# esquematico.net
KiCad netlist of a schematic drawn in Altium Designer
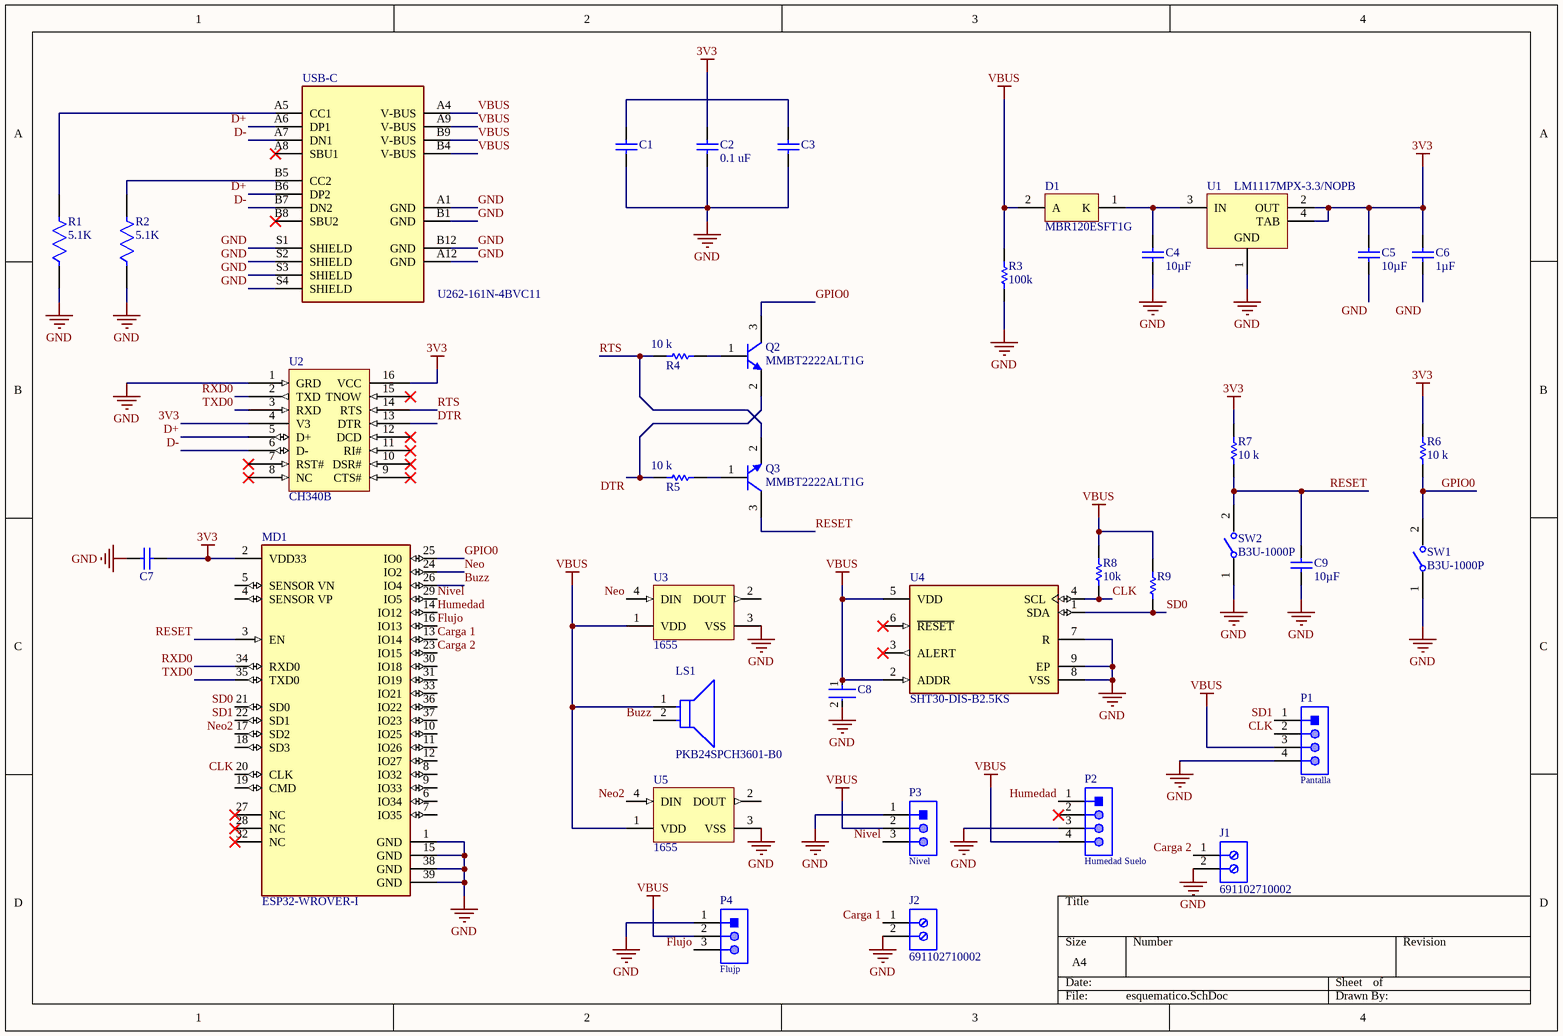
[diagram p0: esquematico.SchDoc]

(export (version "E")
  (design (tool "Eeschema 10.0.6"))
  (components
    (comp (ref "C1")
      (value "C0805C106K4PACTU")
      (footprint "CAPC2013X140X50ML20T25")
      (description "10µF ±10% 16V Ceramic Capacitor X5R 0805 (2012 Metric)")
      (fields (field (name "PART NUMBER") "CL21A106KOQNNNG"))
      (libsource (lib "Altium Content Vault") (part "CAP"))
    )
    (comp (ref "C2")
      (value "0.1 uF")
      (footprint "CAPC2013X94X50ML20T25")
      (description "Chip Capacitor, Ceramic, 0.1 uF, 10%, 50 V, 0805, RoHS, Tape and Reel")
      (fields (field (name "MANUFACTURER") "AVX"))
      (libsource (lib "Altium Content Vault") (part "CAP-NP-2"))
    )
    (comp (ref "C3")
      (value "C0805C106K4PACTU")
      (footprint "CAPC2013X140X50ML20T25")
      (description "10µF ±10% 16V Ceramic Capacitor X5R 0805 (2012 Metric)")
      (fields (field (name "PART NUMBER") "CL21A106KOQNNNG"))
      (libsource (lib "Altium Content Vault") (part "CAP"))
    )
    (comp (ref "C4")
      (value "10µF")
      (footprint "CAPC2013X140X50ML20T25")
      (description "10µF ±10% 16V Ceramic Capacitor X5R 0805 (2012 Metric)")
      (fields (field (name "PART NUMBER") "CL21A106KOQNNNG"))
      (libsource (lib "Altium Content Vault") (part "CAP"))
    )
    (comp (ref "C5")
      (value "10µF")
      (footprint "CAPC2013X140X50ML20T25")
      (description "10µF ±10% 16V Ceramic Capacitor X5R 0805 (2012 Metric)")
      (fields (field (name "PART NUMBER") "CL21A106KOQNNNG"))
      (libsource (lib "Altium Content Vault") (part "CAP"))
    )
    (comp (ref "C6")
      (value "1µF")
      (footprint "CAPC2013X145X50ML20T25")
      (description "1µF ±10% 16V Ceramic Capacitor X7R 0805 (2012 Metric)")
      (fields (field (name "MANUFACTURER") "Kemet") (field (name "PART NUMBER") "C0805C105K4RAC7800"))
      (libsource (lib "Altium Content Vault") (part "CAP"))
    )
    (comp (ref "C7")
      (value "08055C104KAT2A")
      (footprint "CAPC2013X94X50ML20T25")
      (description "Chip Capacitor, Ceramic, 0.1 uF, 10%, 50 V, 0805, RoHS, Tape and Reel")
      (fields (field (name "MANUFACTURER") "AVX"))
      (libsource (lib "Altium Content Vault") (part "CAP-NP-2"))
    )
    (comp (ref "C8")
      (value "C0402C104K8PACTU")
      (footprint "FP-C0402-BB-MFG")
      (description "CAP CER 0.1UF 10V X5R 0402")
      (fields (field (name "MANUFACTURER") "Kemet") (field (name "TOLERANCE") "0.1"))
      (libsource (lib "Altium Content Vault") (part "b4654b650e69147ec39a6b967a45e02"))
    )
    (comp (ref "C9")
      (value "10µF")
      (footprint "CAPC2013X145X50ML20T25")
      (description "10µF ±10% 16V Ceramic Capacitor X7R 0805 (2012 Metric)")
      (fields (field (name "MANUFACTURER") "Kemet") (field (name "PART NUMBER") "C0805C105K4RAC7800"))
      (libsource (lib "Altium Content Vault") (part "CAP"))
    )
    (comp (ref "D1")
      (value "MBR120ESFT1G")
      (footprint "ONSC-SOD-123FL-2-498_V")
      (description "Schottky Power Rectifier, 2-Pin SOD-123, Pb-Free, Tape and Reel")
      (fields (field (name "MANUFACTURER") "On Semiconductor"))
      (libsource (lib "Altium Content Vault") (part "ONSC-D-K1A2-2_A"))
    )
    (comp (ref "J1")
      (value "691102710002")
      (footprint "691102710002")
      (description "Series 102 - 5.00 mm Horizontal Entry Modular with Pressure Clamp WR-TBL, 2 pin")
      (fields (field (name "MANUFACTURER") "Wurth Elektronik") (field (name "PUBLISHER") "WurthElektronik"))
      (libsource (lib "Altium Content Vault") (part "WE-CN-1P-F-TB2"))
    )
    (comp (ref "J2")
      (value "691102710002")
      (footprint "691102710002")
      (description "Series 102 - 5.00 mm Horizontal Entry Modular with Pressure Clamp WR-TBL, 2 pin")
      (fields (field (name "MANUFACTURER") "Wurth Elektronik") (field (name "PUBLISHER") "WurthElektronik"))
      (libsource (lib "Altium Content Vault") (part "WE-CN-1P-F-TB2"))
    )
    (comp (ref "LS1")
      (value "PKB24SPCH3601-B0")
      (footprint "FP-PKB24SPCH3601-B0-MFG")
      (description "AUDIO PIEZO TRANSDUCER 3-15V TH")
      (libsource (lib "Altium Content Vault") (part "1973c4b650225fd2ddacaff6b763965"))
    )
    (comp (ref "MD1")
      (value "ESP32-WROVER-I")
      (footprint "FP-ESP32-WROVER-I-MFG")
      (description "SMD MODULE, ESP32-D0WDQ6, 32MBIT")
      (fields
        (field (name "MANUFACTURER") "Espressif")
        (field (name "OCTOPART") "https://octopart.com/esp32-wrover-i-espressif+systems-89171349")
      )
      (libsource (lib "Altium Content Vault") (part "cbbb37af8bcfe61dfd46ac9418f0340"))
    )
    (comp (ref "P1")
      (value "Pantalla")
      (footprint "61300411121")
      (description "THT Vertical Pin Header WR-PHD, Pitch 2.54 mm, Single Row, 4 pins")
      (fields
        (field (name "MANUFACTURER") "Wurth Elektronik")
        (field (name "PART NUMBER") "61300411121")
        (field (name "PUBLISHER") "WurthElektronik")
      )
      (libsource (lib "Altium Content Vault") (part "WE-CN-1P-M-R4"))
    )
    (comp (ref "P2")
      (value "Humedad Suelo")
      (footprint "61300411121")
      (description "THT Vertical Pin Header WR-PHD, Pitch 2.54 mm, Single Row, 4 pins")
      (fields
        (field (name "MANUFACTURER") "Wurth Elektronik")
        (field (name "PART NUMBER") "61300411121")
        (field (name "PUBLISHER") "WurthElektronik")
      )
      (libsource (lib "Altium Content Vault") (part "WE-CN-1P-M-R4"))
    )
    (comp (ref "P3")
      (value "Nivel")
      (footprint "61300311121")
      (description "THT Vertical Pin Header WR-PHD, Pitch 2.54 mm, Single Row, 3 pins")
      (fields
        (field (name "PART NUMBER") "61300311121")
        (field (name "MANUFACTURER") "Wurth Elektronik")
        (field (name "PUBLISHER") "WurthElektronik")
      )
      (libsource (lib "Altium Content Vault") (part "WE-CN-1P-M-R3"))
    )
    (comp (ref "P4")
      (value "Flujp")
      (footprint "61300311121")
      (description "THT Vertical Pin Header WR-PHD, Pitch 2.54 mm, Single Row, 3 pins")
      (fields
        (field (name "PART NUMBER") "61300311121")
        (field (name "MANUFACTURER") "Wurth Elektronik")
        (field (name "PUBLISHER") "WurthElektronik")
      )
      (libsource (lib "Altium Content Vault") (part "WE-CN-1P-M-R3"))
    )
    (comp (ref "Q2")
      (value "MMBT2222ALT1G")
      (footprint "ONSC-SOT-23-3-318-08_V")
      (description "General Purpose Transistor, NPN Silicon, 3-Pin SOT-23, Pb-Free, Tape and Reel")
      (fields (field (name "MANUFACTURER") "On Semiconductor"))
      (libsource (lib "Altium Content Vault") (part "ONSC-NPN-B1E2C3-3"))
    )
    (comp (ref "Q3")
      (value "MMBT2222ALT1G")
      (footprint "ONSC-SOT-23-3-318-08_V")
      (description "General Purpose Transistor, NPN Silicon, 3-Pin SOT-23, Pb-Free, Tape and Reel")
      (fields (field (name "MANUFACTURER") "On Semiconductor"))
      (libsource (lib "Altium Content Vault") (part "ONSC-NPN-B1E2C3-3"))
    )
    (comp (ref "R1")
      (value "5.1K")
      (footprint "FP-CRCW0805-e3-MFG")
      (description "RES Thick Film, 5.1kΩ, 1%, 0.125W, 100ppm/°C, 0805")
      (fields (field (name "TOLERANCE") "1%"))
      (libsource (lib "Altium Content Vault") (part "1029c3af85768c4190bb7ad29bc67b5"))
    )
    (comp (ref "R2")
      (value "5.1K")
      (footprint "FP-CRCW0805-e3-MFG")
      (description "RES Thick Film, 5.1kΩ, 1%, 0.125W, 100ppm/°C, 0805")
      (fields (field (name "TOLERANCE") "1%"))
      (libsource (lib "Altium Content Vault") (part "1029c3af85768c4190bb7ad29bc67b5"))
    )
    (comp (ref "R3")
      (value "100k")
      (footprint "RESC2013X60X40ML20T25")
      (description "100 kOhms ±0.1% 0.125W, 1/8W Chip Resistor 0805 (2012 Metric) Automotive AEC-Q200 Thin Film")
      (fields (field (name "PART NUMBER") "ERA6AEB104V") (field (name "MANUFACTURER") "Panasonic"))
      (libsource (lib "Altium Content Vault") (part "RES"))
    )
    (comp (ref "R4")
      (value "10 k")
      (footprint "RESC2013X60X30ML20T20")
      (fields (field (name "PART NUMBER") "RK73B2ATTD103J") (field (name "MANUFACTURER") "KOA Speer"))
      (libsource (lib "Altium Content Vault") (part "RES"))
    )
    (comp (ref "R5")
      (value "10 k")
      (footprint "RESC2013X60X30ML20T20")
      (fields (field (name "PART NUMBER") "RK73B2ATTD103J") (field (name "MANUFACTURER") "KOA Speer"))
      (libsource (lib "Altium Content Vault") (part "RES"))
    )
    (comp (ref "R6")
      (value "10 k")
      (footprint "RESC2013X60X30ML20T20")
      (fields (field (name "PART NUMBER") "RK73B2ATTD103J") (field (name "MANUFACTURER") "KOA Speer"))
      (libsource (lib "Altium Content Vault") (part "RES"))
    )
    (comp (ref "R7")
      (value "10 k")
      (footprint "RESC2013X60X30ML20T20")
      (fields (field (name "PART NUMBER") "RK73B2ATTD103J") (field (name "MANUFACTURER") "KOA Speer"))
      (libsource (lib "Altium Content Vault") (part "RES"))
    )
    (comp (ref "R8")
      (value "10k")
      (footprint "RESC1005X40X25LL05T10")
      (fields (field (name "PART NUMBER") "RC0402FR-0710KL") (field (name "MANUFACTURER") "Yageo / Phycomp"))
      (libsource (lib "Altium Content Vault") (part "RES"))
    )
    (comp (ref "R9")
      (value "10k")
      (footprint "RESC1005X40X25LL05T10")
      (fields (field (name "PART NUMBER") "RC0402FR-0710KL") (field (name "MANUFACTURER") "Yageo / Phycomp"))
      (libsource (lib "Altium Content Vault") (part "RES"))
    )
    (comp (ref "SW1")
      (value "B3U-1000P")
      (footprint "FP-B3U-1000P-MFG")
      (description "SWITCH TACTILE SPST-NO 0.05A 12V")
      (libsource (lib "Altium Content Vault") (part "ae622034201233ca1abcedc05908f33"))
    )
    (comp (ref "SW2")
      (value "B3U-1000P")
      (footprint "FP-B3U-1000P-MFG")
      (description "SWITCH TACTILE SPST-NO 0.05A 12V")
      (libsource (lib "Altium Content Vault") (part "ae622034201233ca1abcedc05908f33"))
    )
    (comp (ref "U1")
      (value "LM1117MPX-3.3/NOPB")
      (footprint "DCY0004A_M")
      (description "800mA Low-Dropout Linear Regulator, 4-pin SOT-223, Pb-Free")
      (fields (field (name "MANUFACTURER") "Texas Instruments"))
      (libsource (lib "Altium Content Vault") (part "PM-REG-LM1086-SOT4"))
    )
    (comp (ref "U2")
      (value "CH340B")
      (footprint "CH340B")
      (description "- USB 2.0 Transceiver 2Mbps SOP-16_150mil USB ICs ROHS")
      (libsource (lib "Schlib1") (part "CH340B"))
    )
    (comp (ref "U3")
      (value "1655")
      (footprint "ADA-RGB-1655_V")
      (fields (field (name "MANUFACTURER") "Adafruit-Industries-LLC"))
      (libsource (lib "Altium Content Vault") (part "ADA-RGB-1655-4"))
    )
    (comp (ref "U4")
      (value "SHT30-DIS-B2.5KS")
      (footprint "FP-SHT30-DIS-B2_5KS-MFG")
      (description "SENSOR HUMID/TEMP 5V I2C 3% SMD")
      (libsource (lib "Altium Content Vault") (part "3a40f6fddac460f1c5fb2adec20f0f2"))
    )
    (comp (ref "U5")
      (value "1655")
      (footprint "ADA-RGB-1655_V")
      (fields (field (name "MANUFACTURER") "Adafruit-Industries-LLC"))
      (libsource (lib "Altium Content Vault") (part "ADA-RGB-1655-4"))
    )
    (comp (ref "USB-C")
      (value "U262-161N-4BVC11")
      (footprint "U262-161N-4BVC11")
      (description "USB - Type C Female 16 SMT USB Connectors RoHS")
      (libsource (lib "Schlib1") (part "U262-161N-4BVC11"))
    )
  )
  (nets
    (net (code "1") (name "/Buzz") (class "Default")
      (node (ref "LS1") (pin "2") (pinfunction "A_2") (pintype "passive"))
      (node (ref "MD1") (pin "26") (pinfunction "IO4_26") (pintype "bidirectional"))
    )
    (net (code "2") (name "/CLK") (class "Default")
      (node (ref "MD1") (pin "20") (pinfunction "CLK_20") (pintype "bidirectional"))
      (node (ref "P1") (pin "2") (pinfunction "2_2") (pintype "passive"))
      (node (ref "R8") (pin "2") (pinfunction "2_2") (pintype "passive"))
      (node (ref "U4") (pin "4") (pinfunction "SCL_4") (pintype "bidirectional"))
    )
    (net (code "3") (name "/Carga 1") (class "Default")
      (node (ref "J2") (pin "1") (pinfunction "1_1") (pintype "passive"))
      (node (ref "MD1") (pin "13") (pinfunction "IO14_13") (pintype "bidirectional"))
    )
    (net (code "4") (name "/Carga 2") (class "Default")
      (node (ref "J1") (pin "1") (pinfunction "1_1") (pintype "passive"))
      (node (ref "MD1") (pin "23") (pinfunction "IO15_23") (pintype "bidirectional"))
    )
    (net (code "5") (name "/D+") (class "Default")
      (node (ref "U2") (pin "5") (pinfunction "D+_5") (pintype "bidirectional"))
      (node (ref "USB-C") (pin "A6") (pinfunction "DP1_A6") (pintype "power_in"))
      (node (ref "USB-C") (pin "B6") (pinfunction "DP2_B6") (pintype "power_in"))
    )
    (net (code "6") (name "/D-") (class "Default")
      (node (ref "U2") (pin "6") (pinfunction "D-_6") (pintype "bidirectional"))
      (node (ref "USB-C") (pin "A7") (pinfunction "DN1_A7") (pintype "power_in"))
      (node (ref "USB-C") (pin "B7") (pinfunction "DN2_B7") (pintype "power_in"))
    )
    (net (code "7") (name "/DTR") (class "Default")
      (node (ref "Q2") (pin "2") (pinfunction "E_2") (pintype "passive"))
      (node (ref "R5") (pin "2") (pinfunction "2_2") (pintype "passive"))
      (node (ref "U2") (pin "13") (pinfunction "DTR_13") (pintype "input"))
    )
    (net (code "8") (name "/Flujo") (class "Default")
      (node (ref "MD1") (pin "16") (pinfunction "IO13_16") (pintype "bidirectional"))
      (node (ref "P4") (pin "3") (pinfunction "3_3") (pintype "passive"))
    )
    (net (code "9") (name "/GPIO0") (class "Default")
      (node (ref "MD1") (pin "25") (pinfunction "IO0_25") (pintype "bidirectional"))
      (node (ref "Q2") (pin "3") (pinfunction "C_3") (pintype "passive"))
      (node (ref "R6") (pin "1") (pinfunction "1_1") (pintype "passive"))
      (node (ref "SW1") (pin "2") (pinfunction "2_2") (pintype "passive"))
    )
    (net (code "10") (name "/Humedad") (class "Default")
      (node (ref "MD1") (pin "14") (pinfunction "IO12_14") (pintype "bidirectional"))
      (node (ref "P2") (pin "1") (pinfunction "1_1") (pintype "passive"))
    )
    (net (code "11") (name "/Neo") (class "Default")
      (node (ref "MD1") (pin "24") (pinfunction "IO2_24") (pintype "bidirectional"))
      (node (ref "U3") (pin "4") (pinfunction "DIN_4") (pintype "input"))
    )
    (net (code "12") (name "/Neo2") (class "Default")
      (node (ref "MD1") (pin "17") (pinfunction "SD2_17") (pintype "bidirectional"))
      (node (ref "U5") (pin "4") (pinfunction "DIN_4") (pintype "input"))
    )
    (net (code "13") (name "/Nivel") (class "Default")
      (node (ref "MD1") (pin "29") (pinfunction "IO5_29") (pintype "bidirectional"))
      (node (ref "P3") (pin "3") (pinfunction "3_3") (pintype "passive"))
    )
    (net (code "14") (name "/RESET") (class "Default")
      (node (ref "C9") (pin "2") (pinfunction "2_2") (pintype "passive"))
      (node (ref "MD1") (pin "3") (pinfunction "EN_3") (pintype "input"))
      (node (ref "Q3") (pin "3") (pinfunction "C_3") (pintype "passive"))
      (node (ref "R7") (pin "1") (pinfunction "1_1") (pintype "passive"))
      (node (ref "SW2") (pin "2") (pinfunction "2_2") (pintype "passive"))
    )
    (net (code "15") (name "/RTS") (class "Default")
      (node (ref "Q3") (pin "2") (pinfunction "E_2") (pintype "passive"))
      (node (ref "R4") (pin "2") (pinfunction "2_2") (pintype "passive"))
      (node (ref "U2") (pin "14") (pinfunction "RTS_14") (pintype "input"))
    )
    (net (code "16") (name "/RXD0") (class "Default")
      (node (ref "MD1") (pin "34") (pinfunction "RXD0_34") (pintype "bidirectional"))
      (node (ref "U2") (pin "2") (pinfunction "TXD_2") (pintype "output"))
    )
    (net (code "17") (name "/SD0") (class "Default")
      (node (ref "MD1") (pin "21") (pinfunction "SD0_21") (pintype "bidirectional"))
      (node (ref "R9") (pin "2") (pinfunction "2_2") (pintype "passive"))
      (node (ref "U4") (pin "1") (pinfunction "SDA_1") (pintype "bidirectional"))
    )
    (net (code "18") (name "/SD1") (class "Default")
      (node (ref "MD1") (pin "22") (pinfunction "SD1_22") (pintype "bidirectional"))
      (node (ref "P1") (pin "1") (pinfunction "1_1") (pintype "passive"))
    )
    (net (code "19") (name "/TXD0") (class "Default")
      (node (ref "MD1") (pin "35") (pinfunction "TXD0_35") (pintype "bidirectional"))
      (node (ref "U2") (pin "3") (pinfunction "RXD_3") (pintype "input"))
    )
    (net (code "20") (name "3V3") (class "Default")
      (node (ref "C2") (pin "2") (pinfunction "2_2") (pintype "passive"))
      (node (ref "C5") (pin "2") (pinfunction "2_2") (pintype "passive"))
      (node (ref "C6") (pin "2") (pinfunction "2_2") (pintype "passive"))
      (node (ref "C7") (pin "2") (pinfunction "2_2") (pintype "passive"))
      (node (ref "MD1") (pin "2") (pinfunction "VDD33_2") (pintype "power_in"))
      (node (ref "R6") (pin "2") (pinfunction "2_2") (pintype "passive"))
      (node (ref "R7") (pin "2") (pinfunction "2_2") (pintype "passive"))
      (node (ref "U1") (pin "2") (pinfunction "OUT_2") (pintype "power_in"))
      (node (ref "U1") (pin "4") (pinfunction "TAB_4") (pintype "power_in"))
      (node (ref "U2") (pin "16") (pinfunction "VCC_16") (pintype "power_in"))
      (node (ref "U2") (pin "4") (pinfunction "V3_4") (pintype "power_in"))
    )
    (net (code "21") (name "GND") (class "Default")
      (node (ref "C1") (pin "1") (pinfunction "1_1") (pintype "passive"))
      (node (ref "C2") (pin "1") (pinfunction "1_1") (pintype "passive"))
      (node (ref "C3") (pin "1") (pinfunction "1_1") (pintype "passive"))
      (node (ref "C4") (pin "1") (pinfunction "1_1") (pintype "passive"))
      (node (ref "C5") (pin "1") (pinfunction "1_1") (pintype "passive"))
      (node (ref "C6") (pin "1") (pinfunction "1_1") (pintype "passive"))
      (node (ref "C7") (pin "1") (pinfunction "1_1") (pintype "passive"))
      (node (ref "C8") (pin "2") (pinfunction "2_2") (pintype "passive"))
      (node (ref "C9") (pin "1") (pinfunction "1_1") (pintype "passive"))
      (node (ref "J1") (pin "2") (pinfunction "2_2") (pintype "passive"))
      (node (ref "J2") (pin "2") (pinfunction "2_2") (pintype "passive"))
      (node (ref "MD1") (pin "1") (pinfunction "GND_1") (pintype "power_in"))
      (node (ref "MD1") (pin "15") (pinfunction "GND_15") (pintype "power_in"))
      (node (ref "MD1") (pin "38") (pinfunction "GND_38") (pintype "power_in"))
      (node (ref "MD1") (pin "39") (pinfunction "GND_39") (pintype "power_in"))
      (node (ref "P1") (pin "4") (pinfunction "4_4") (pintype "passive"))
      (node (ref "P2") (pin "3") (pinfunction "3_3") (pintype "passive"))
      (node (ref "P3") (pin "1") (pinfunction "1_1") (pintype "passive"))
      (node (ref "P4") (pin "1") (pinfunction "1_1") (pintype "passive"))
      (node (ref "R1") (pin "1") (pinfunction "1_1") (pintype "passive"))
      (node (ref "R2") (pin "1") (pinfunction "1_1") (pintype "passive"))
      (node (ref "R3") (pin "1") (pinfunction "1_1") (pintype "passive"))
      (node (ref "SW1") (pin "1") (pinfunction "1_1") (pintype "passive"))
      (node (ref "SW2") (pin "1") (pinfunction "1_1") (pintype "passive"))
      (node (ref "U1") (pin "1") (pinfunction "GND_1") (pintype "power_in"))
      (node (ref "U2") (pin "1") (pinfunction "GRD_1") (pintype "input"))
      (node (ref "U3") (pin "3") (pinfunction "VSS_3") (pintype "power_in"))
      (node (ref "U4") (pin "7") (pinfunction "R_7") (pintype "passive"))
      (node (ref "U4") (pin "8") (pinfunction "VSS_8") (pintype "power_in"))
      (node (ref "U4") (pin "9") (pinfunction "EP_9") (pintype "passive"))
      (node (ref "U5") (pin "3") (pinfunction "VSS_3") (pintype "power_in"))
      (node (ref "USB-C") (pin "A1") (pinfunction "GND_A1") (pintype "power_in"))
      (node (ref "USB-C") (pin "A12") (pinfunction "GND_A12") (pintype "power_in"))
      (node (ref "USB-C") (pin "B1") (pinfunction "GND_B1") (pintype "power_in"))
      (node (ref "USB-C") (pin "B12") (pinfunction "GND_B12") (pintype "power_in"))
      (node (ref "USB-C") (pin "S1") (pinfunction "SHIELD_S1") (pintype "passive"))
      (node (ref "USB-C") (pin "S2") (pinfunction "SHIELD_S2") (pintype "passive"))
      (node (ref "USB-C") (pin "S3") (pinfunction "SHIELD_S3") (pintype "passive"))
      (node (ref "USB-C") (pin "S4") (pinfunction "SHIELD_S4") (pintype "passive"))
    )
    (net (code "22") (name "Net-(C1-Pad2)") (class "Default")
      (node (ref "C1") (pin "2") (pinfunction "2_2") (pintype "passive"))
      (node (ref "C3") (pin "2") (pinfunction "2_2") (pintype "passive"))
    )
    (net (code "23") (name "Net-(D1-K)") (class "Default")
      (node (ref "C4") (pin "2") (pinfunction "2_2") (pintype "passive"))
      (node (ref "D1") (pin "1") (pinfunction "K_1") (pintype "passive"))
      (node (ref "U1") (pin "3") (pinfunction "IN_3") (pintype "power_in"))
    )
    (net (code "24") (name "Net-(Q2-B)") (class "Default")
      (node (ref "Q2") (pin "1") (pinfunction "B_1") (pintype "passive"))
      (node (ref "R4") (pin "1") (pinfunction "1_1") (pintype "passive"))
    )
    (net (code "25") (name "Net-(Q3-B)") (class "Default")
      (node (ref "Q3") (pin "1") (pinfunction "B_1") (pintype "passive"))
      (node (ref "R5") (pin "1") (pinfunction "1_1") (pintype "passive"))
    )
    (net (code "26") (name "Net-(USB-C-CC1)") (class "Default")
      (node (ref "R1") (pin "2") (pinfunction "2_2") (pintype "passive"))
      (node (ref "USB-C") (pin "A5") (pinfunction "CC1_A5") (pintype "power_in"))
    )
    (net (code "27") (name "Net-(USB-C-CC2)") (class "Default")
      (node (ref "R2") (pin "2") (pinfunction "2_2") (pintype "passive"))
      (node (ref "USB-C") (pin "B5") (pinfunction "CC2_B5") (pintype "power_in"))
    )
    (net (code "28") (name "VBUS") (class "Default")
      (node (ref "C8") (pin "1") (pinfunction "1_1") (pintype "passive"))
      (node (ref "D1") (pin "2") (pinfunction "A_2") (pintype "passive"))
      (node (ref "LS1") (pin "1") (pinfunction "C_1") (pintype "passive"))
      (node (ref "P1") (pin "3") (pinfunction "3_3") (pintype "passive"))
      (node (ref "P2") (pin "4") (pinfunction "4_4") (pintype "passive"))
      (node (ref "P3") (pin "2") (pinfunction "2_2") (pintype "passive"))
      (node (ref "P4") (pin "2") (pinfunction "2_2") (pintype "passive"))
      (node (ref "R3") (pin "2") (pinfunction "2_2") (pintype "passive"))
      (node (ref "R8") (pin "1") (pinfunction "1_1") (pintype "passive"))
      (node (ref "R9") (pin "1") (pinfunction "1_1") (pintype "passive"))
      (node (ref "U3") (pin "1") (pinfunction "VDD_1") (pintype "power_in"))
      (node (ref "U4") (pin "2") (pinfunction "ADDR_2") (pintype "input"))
      (node (ref "U4") (pin "5") (pinfunction "VDD_5") (pintype "power_in"))
      (node (ref "U5") (pin "1") (pinfunction "VDD_1") (pintype "power_in"))
      (node (ref "USB-C") (pin "A4") (pinfunction "V-BUS_A4") (pintype "power_in"))
      (node (ref "USB-C") (pin "A9") (pinfunction "V-BUS_A9") (pintype "power_in"))
      (node (ref "USB-C") (pin "B4") (pinfunction "V-BUS_B4") (pintype "power_in"))
      (node (ref "USB-C") (pin "B9") (pinfunction "V-BUS_B9") (pintype "power_in"))
    )
    (net (code "29") (name "unconnected-(MD1-CMD-Pad19)") (class "Default")
      (node (ref "MD1") (pin "19") (pinfunction "CMD_19") (pintype "bidirectional"))
    )
    (net (code "30") (name "unconnected-(MD1-IO18-Pad30)") (class "Default")
      (node (ref "MD1") (pin "30") (pinfunction "IO18_30") (pintype "bidirectional"))
    )
    (net (code "31") (name "unconnected-(MD1-IO19-Pad31)") (class "Default")
      (node (ref "MD1") (pin "31") (pinfunction "IO19_31") (pintype "bidirectional"))
    )
    (net (code "32") (name "unconnected-(MD1-IO21-Pad33)") (class "Default")
      (node (ref "MD1") (pin "33") (pinfunction "IO21_33") (pintype "bidirectional"))
    )
    (net (code "33") (name "unconnected-(MD1-IO22-Pad36)") (class "Default")
      (node (ref "MD1") (pin "36") (pinfunction "IO22_36") (pintype "bidirectional"))
    )
    (net (code "34") (name "unconnected-(MD1-IO23-Pad37)") (class "Default")
      (node (ref "MD1") (pin "37") (pinfunction "IO23_37") (pintype "bidirectional"))
    )
    (net (code "35") (name "unconnected-(MD1-IO25-Pad10)") (class "Default")
      (node (ref "MD1") (pin "10") (pinfunction "IO25_10") (pintype "bidirectional"))
    )
    (net (code "36") (name "unconnected-(MD1-IO26-Pad11)") (class "Default")
      (node (ref "MD1") (pin "11") (pinfunction "IO26_11") (pintype "bidirectional"))
    )
    (net (code "37") (name "unconnected-(MD1-IO27-Pad12)") (class "Default")
      (node (ref "MD1") (pin "12") (pinfunction "IO27_12") (pintype "bidirectional"))
    )
    (net (code "38") (name "unconnected-(MD1-IO32-Pad8)") (class "Default")
      (node (ref "MD1") (pin "8") (pinfunction "IO32_8") (pintype "bidirectional"))
    )
    (net (code "39") (name "unconnected-(MD1-IO33-Pad9)") (class "Default")
      (node (ref "MD1") (pin "9") (pinfunction "IO33_9") (pintype "bidirectional"))
    )
    (net (code "40") (name "unconnected-(MD1-IO34-Pad6)") (class "Default")
      (node (ref "MD1") (pin "6") (pinfunction "IO34_6") (pintype "bidirectional"))
    )
    (net (code "41") (name "unconnected-(MD1-IO35-Pad7)") (class "Default")
      (node (ref "MD1") (pin "7") (pinfunction "IO35_7") (pintype "bidirectional"))
    )
    (net (code "42") (name "unconnected-(MD1-NC-Pad27)") (class "Default")
      (node (ref "MD1") (pin "27") (pinfunction "NC_27") (pintype "passive+no_connect"))
    )
    (net (code "43") (name "unconnected-(MD1-NC-Pad28)") (class "Default")
      (node (ref "MD1") (pin "28") (pinfunction "NC_28") (pintype "passive+no_connect"))
    )
    (net (code "44") (name "unconnected-(MD1-NC-Pad32)") (class "Default")
      (node (ref "MD1") (pin "32") (pinfunction "NC_32") (pintype "passive+no_connect"))
    )
    (net (code "45") (name "unconnected-(MD1-SD3-Pad18)") (class "Default")
      (node (ref "MD1") (pin "18") (pinfunction "SD3_18") (pintype "bidirectional"))
    )
    (net (code "46") (name "unconnected-(MD1-SENSOR_VN-Pad5)") (class "Default")
      (node (ref "MD1") (pin "5") (pinfunction "SENSOR_VN_5") (pintype "bidirectional"))
    )
    (net (code "47") (name "unconnected-(MD1-SENSOR_VP-Pad4)") (class "Default")
      (node (ref "MD1") (pin "4") (pinfunction "SENSOR_VP_4") (pintype "bidirectional"))
    )
    (net (code "48") (name "unconnected-(P2-Pad2)") (class "Default")
      (node (ref "P2") (pin "2") (pinfunction "2_2") (pintype "passive+no_connect"))
    )
    (net (code "49") (name "unconnected-(U2-CTS#-Pad9)") (class "Default")
      (node (ref "U2") (pin "9") (pinfunction "CTS#_9") (pintype "input+no_connect"))
    )
    (net (code "50") (name "unconnected-(U2-DCD-Pad12)") (class "Default")
      (node (ref "U2") (pin "12") (pinfunction "DCD_12") (pintype "input+no_connect"))
    )
    (net (code "51") (name "unconnected-(U2-DSR#-Pad10)") (class "Default")
      (node (ref "U2") (pin "10") (pinfunction "DSR#_10") (pintype "input+no_connect"))
    )
    (net (code "52") (name "unconnected-(U2-NC-Pad8)") (class "Default")
      (node (ref "U2") (pin "8") (pinfunction "NC_8") (pintype "input+no_connect"))
    )
    (net (code "53") (name "unconnected-(U2-RI#-Pad11)") (class "Default")
      (node (ref "U2") (pin "11") (pinfunction "RI#_11") (pintype "input+no_connect"))
    )
    (net (code "54") (name "unconnected-(U2-RST#-Pad7)") (class "Default")
      (node (ref "U2") (pin "7") (pinfunction "RST#_7") (pintype "input+no_connect"))
    )
    (net (code "55") (name "unconnected-(U2-TNOW-Pad15)") (class "Default")
      (node (ref "U2") (pin "15") (pinfunction "TNOW_15") (pintype "input+no_connect"))
    )
    (net (code "56") (name "unconnected-(U3-DOUT-Pad2)") (class "Default")
      (node (ref "U3") (pin "2") (pinfunction "DOUT_2") (pintype "output"))
    )
    (net (code "57") (name "unconnected-(U4-ALERT-Pad3)") (class "Default")
      (node (ref "U4") (pin "3") (pinfunction "ALERT_3") (pintype "output+no_connect"))
    )
    (net (code "58") (name "unconnected-(U4-~{RESET}-Pad6)") (class "Default")
      (node (ref "U4") (pin "6") (pinfunction "~{RESET}_6") (pintype "input+no_connect"))
    )
    (net (code "59") (name "unconnected-(U5-DOUT-Pad2)") (class "Default")
      (node (ref "U5") (pin "2") (pinfunction "DOUT_2") (pintype "output"))
    )
    (net (code "60") (name "unconnected-(USB-C-SBU1-PadA8)") (class "Default")
      (node (ref "USB-C") (pin "A8") (pinfunction "SBU1_A8") (pintype "power_in+no_connect"))
    )
    (net (code "61") (name "unconnected-(USB-C-SBU2-PadB8)") (class "Default")
      (node (ref "USB-C") (pin "B8") (pinfunction "SBU2_B8") (pintype "power_in+no_connect"))
    )
  )
)
